# driver.net
KiCad netlist of a schematic drawn in EAGLE
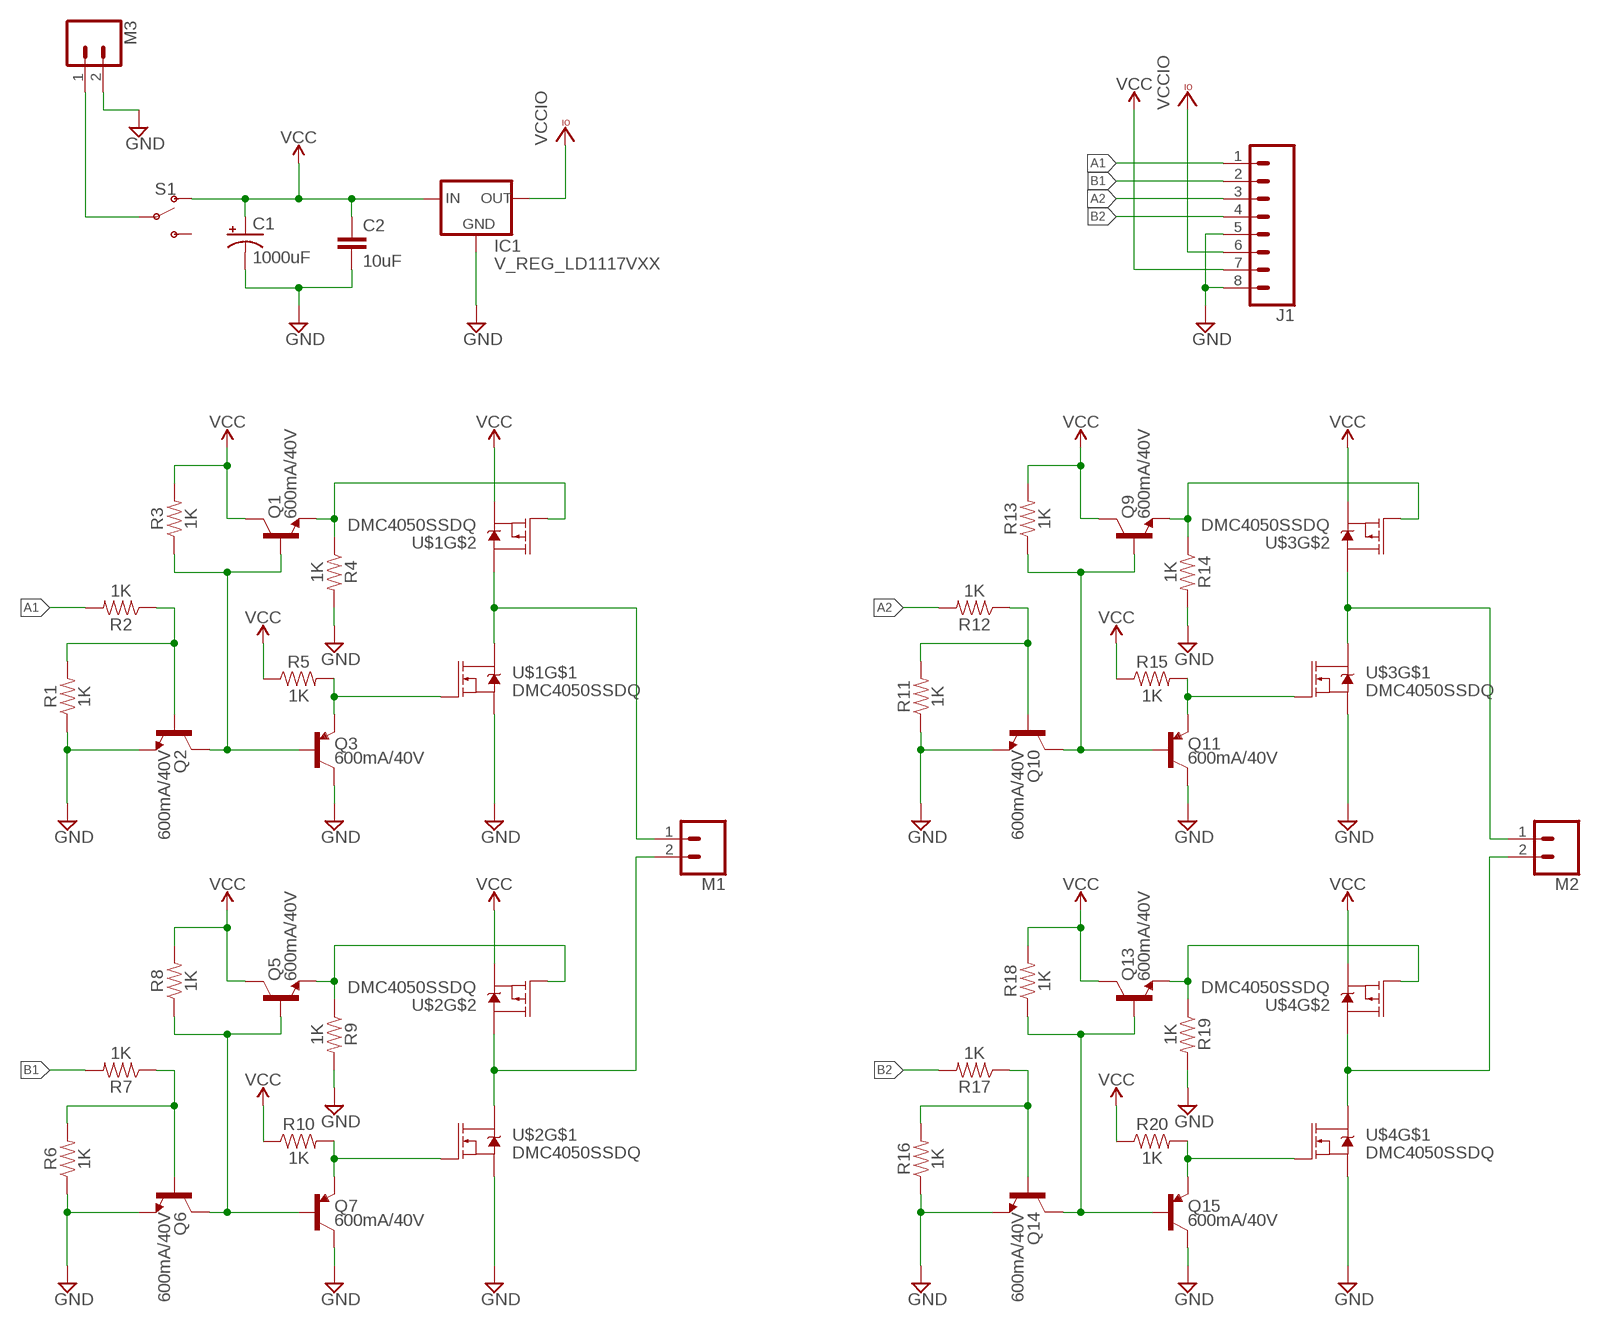
[diagram p0: schematic, sheet 1]

(export (version "E")
  (design (tool "Eeschema 10.0.6"))
  (components
    (comp (ref "C1")
      (value "1000uF")
      (footprint "eagle-import:CPOL-RADIAL-5MM-10MM")
      (libsource (lib "eagle-import") (part "1000UF-RADIAL-5MM-25V-20%"))
    )
    (comp (ref "C2")
      (value "10uF")
      (footprint "eagle-import:0805")
      (libsource (lib "eagle-import") (part "1.0UF-0805-25V-10%"))
    )
    (comp (ref "IC1")
      (value "V_REG_LD1117VXX")
      (footprint "eagle-import:78XXL")
      (libsource (lib "eagle-import") (part "V_REG_LD1117VXX"))
    )
    (comp (ref "J1")
      (value "CONN_08\"")
      (footprint "eagle-import:1X08")
      (libsource (lib "eagle-import") (part "CONN_08{dblquote}"))
    )
    (comp (ref "M1")
      (value "CONN_023.5MM")
      (footprint "eagle-import:SCREWTERMINAL-3.5MM-2")
      (libsource (lib "eagle-import") (part "CONN_023.5MM"))
    )
    (comp (ref "M2")
      (value "CONN_023.5MM")
      (footprint "eagle-import:SCREWTERMINAL-3.5MM-2")
      (libsource (lib "eagle-import") (part "CONN_023.5MM"))
    )
    (comp (ref "M3")
      (value "CONN_023.5MM")
      (footprint "eagle-import:SCREWTERMINAL-3.5MM-2")
      (libsource (lib "eagle-import") (part "CONN_023.5MM"))
    )
    (comp (ref "Q1")
      (value "600mA/40V")
      (footprint "eagle-import:SOT23-3")
      (libsource (lib "eagle-import") (part "TRANS_NPN-MMBT2222AL"))
    )
    (comp (ref "Q2")
      (value "600mA/40V")
      (footprint "eagle-import:SOT23-3")
      (libsource (lib "eagle-import") (part "TRANS_NPN-MMBT2222AL"))
    )
    (comp (ref "Q3")
      (value "600mA/40V")
      (footprint "eagle-import:SOT23-3")
      (libsource (lib "eagle-import") (part "TRANS_PNP-MMBT4403"))
    )
    (comp (ref "Q5")
      (value "600mA/40V")
      (footprint "eagle-import:SOT23-3")
      (libsource (lib "eagle-import") (part "TRANS_NPN-MMBT2222AL"))
    )
    (comp (ref "Q6")
      (value "600mA/40V")
      (footprint "eagle-import:SOT23-3")
      (libsource (lib "eagle-import") (part "TRANS_NPN-MMBT2222AL"))
    )
    (comp (ref "Q7")
      (value "600mA/40V")
      (footprint "eagle-import:SOT23-3")
      (libsource (lib "eagle-import") (part "TRANS_PNP-MMBT4403"))
    )
    (comp (ref "Q9")
      (value "600mA/40V")
      (footprint "eagle-import:SOT23-3")
      (libsource (lib "eagle-import") (part "TRANS_NPN-MMBT2222AL"))
    )
    (comp (ref "Q10")
      (value "600mA/40V")
      (footprint "eagle-import:SOT23-3")
      (libsource (lib "eagle-import") (part "TRANS_NPN-MMBT2222AL"))
    )
    (comp (ref "Q11")
      (value "600mA/40V")
      (footprint "eagle-import:SOT23-3")
      (libsource (lib "eagle-import") (part "TRANS_PNP-MMBT4403"))
    )
    (comp (ref "Q13")
      (value "600mA/40V")
      (footprint "eagle-import:SOT23-3")
      (libsource (lib "eagle-import") (part "TRANS_NPN-MMBT2222AL"))
    )
    (comp (ref "Q14")
      (value "600mA/40V")
      (footprint "eagle-import:SOT23-3")
      (libsource (lib "eagle-import") (part "TRANS_NPN-MMBT2222AL"))
    )
    (comp (ref "Q15")
      (value "600mA/40V")
      (footprint "eagle-import:SOT23-3")
      (libsource (lib "eagle-import") (part "TRANS_PNP-MMBT4403"))
    )
    (comp (ref "R1")
      (value "1K")
      (footprint "eagle-import:0805")
      (libsource (lib "eagle-import") (part "RESISTOR0805"))
    )
    (comp (ref "R2")
      (value "1K")
      (footprint "eagle-import:0805")
      (libsource (lib "eagle-import") (part "RESISTOR0805"))
    )
    (comp (ref "R3")
      (value "1K")
      (footprint "eagle-import:0805")
      (libsource (lib "eagle-import") (part "RESISTOR0805"))
    )
    (comp (ref "R4")
      (value "1K")
      (footprint "eagle-import:0805")
      (libsource (lib "eagle-import") (part "RESISTOR0805"))
    )
    (comp (ref "R5")
      (value "1K")
      (footprint "eagle-import:0805")
      (libsource (lib "eagle-import") (part "RESISTOR0805"))
    )
    (comp (ref "R6")
      (value "1K")
      (footprint "eagle-import:0805")
      (libsource (lib "eagle-import") (part "RESISTOR0805"))
    )
    (comp (ref "R7")
      (value "1K")
      (footprint "eagle-import:0805")
      (libsource (lib "eagle-import") (part "RESISTOR0805"))
    )
    (comp (ref "R8")
      (value "1K")
      (footprint "eagle-import:0805")
      (libsource (lib "eagle-import") (part "RESISTOR0805"))
    )
    (comp (ref "R9")
      (value "1K")
      (footprint "eagle-import:0805")
      (libsource (lib "eagle-import") (part "RESISTOR0805"))
    )
    (comp (ref "R10")
      (value "1K")
      (footprint "eagle-import:0805")
      (libsource (lib "eagle-import") (part "RESISTOR0805"))
    )
    (comp (ref "R11")
      (value "1K")
      (footprint "eagle-import:0805")
      (libsource (lib "eagle-import") (part "RESISTOR0805"))
    )
    (comp (ref "R12")
      (value "1K")
      (footprint "eagle-import:0805")
      (libsource (lib "eagle-import") (part "RESISTOR0805"))
    )
    (comp (ref "R13")
      (value "1K")
      (footprint "eagle-import:0805")
      (libsource (lib "eagle-import") (part "RESISTOR0805"))
    )
    (comp (ref "R14")
      (value "1K")
      (footprint "eagle-import:0805")
      (libsource (lib "eagle-import") (part "RESISTOR0805"))
    )
    (comp (ref "R15")
      (value "1K")
      (footprint "eagle-import:0805")
      (libsource (lib "eagle-import") (part "RESISTOR0805"))
    )
    (comp (ref "R16")
      (value "1K")
      (footprint "eagle-import:0805")
      (libsource (lib "eagle-import") (part "RESISTOR0805"))
    )
    (comp (ref "R17")
      (value "1K")
      (footprint "eagle-import:0805")
      (libsource (lib "eagle-import") (part "RESISTOR0805"))
    )
    (comp (ref "R18")
      (value "1K")
      (footprint "eagle-import:0805")
      (libsource (lib "eagle-import") (part "RESISTOR0805"))
    )
    (comp (ref "R19")
      (value "1K")
      (footprint "eagle-import:0805")
      (libsource (lib "eagle-import") (part "RESISTOR0805"))
    )
    (comp (ref "R20")
      (value "1K")
      (footprint "eagle-import:0805")
      (libsource (lib "eagle-import") (part "RESISTOR0805"))
    )
    (comp (ref "S1")
      (value "SWITCH-SPDT-PTH-11.6X4.0MM")
      (footprint "eagle-import:SWITCH_SPDT_PTH_11.6X4.0MM")
      (libsource (lib "eagle-import") (part "SWITCH-SPDT-PTH-11.6X4.0MM"))
    )
    (comp (ref "U$1")
      (value "DMC4050SSDQ")
      (footprint "eagle-import:SO08")
      (libsource (lib "eagle-import") (part "DMC4050SSDQ"))
    )
    (comp (ref "U$2")
      (value "DMC4050SSDQ")
      (footprint "eagle-import:SO08")
      (libsource (lib "eagle-import") (part "DMC4050SSDQ"))
    )
    (comp (ref "U$3")
      (value "DMC4050SSDQ")
      (footprint "eagle-import:SO08")
      (libsource (lib "eagle-import") (part "DMC4050SSDQ"))
    )
    (comp (ref "U$4")
      (value "DMC4050SSDQ")
      (footprint "eagle-import:SO08")
      (libsource (lib "eagle-import") (part "DMC4050SSDQ"))
    )
  )
  (nets
    (net (code "1") (name "A1") (class "Default")
      (node (ref "J1") (pin "1") (pinfunction "1_1") (pintype "passive"))
      (node (ref "R2") (pin "2") (pinfunction "2_2") (pintype "passive"))
    )
    (net (code "2") (name "A2") (class "Default")
      (node (ref "J1") (pin "3") (pinfunction "3_3") (pintype "passive"))
      (node (ref "R12") (pin "2") (pinfunction "2_2") (pintype "passive"))
    )
    (net (code "3") (name "B1") (class "Default")
      (node (ref "J1") (pin "2") (pinfunction "2_2") (pintype "passive"))
      (node (ref "R7") (pin "2") (pinfunction "2_2") (pintype "passive"))
    )
    (net (code "4") (name "B2") (class "Default")
      (node (ref "J1") (pin "4") (pinfunction "4_4") (pintype "passive"))
      (node (ref "R17") (pin "2") (pinfunction "2_2") (pintype "passive"))
    )
    (net (code "5") (name "GND") (class "Default")
      (node (ref "C1") (pin "-") (pinfunction "-_-") (pintype "passive"))
      (node (ref "C2") (pin "2") (pinfunction "2_2") (pintype "passive"))
      (node (ref "IC1") (pin "IN") (pinfunction "GND_IN") (pintype "input"))
      (node (ref "J1") (pin "5") (pinfunction "5_5") (pintype "passive"))
      (node (ref "J1") (pin "8") (pinfunction "8_8") (pintype "passive"))
      (node (ref "M3") (pin "2") (pinfunction "2_2") (pintype "passive"))
      (node (ref "Q10") (pin "2") (pinfunction "E_2") (pintype "passive"))
      (node (ref "Q11") (pin "3") (pinfunction "C_3") (pintype "passive"))
      (node (ref "Q14") (pin "2") (pinfunction "E_2") (pintype "passive"))
      (node (ref "Q15") (pin "3") (pinfunction "C_3") (pintype "passive"))
      (node (ref "Q2") (pin "2") (pinfunction "E_2") (pintype "passive"))
      (node (ref "Q3") (pin "3") (pinfunction "C_3") (pintype "passive"))
      (node (ref "Q6") (pin "2") (pinfunction "E_2") (pintype "passive"))
      (node (ref "Q7") (pin "3") (pinfunction "C_3") (pintype "passive"))
      (node (ref "R1") (pin "1") (pinfunction "1_1") (pintype "passive"))
      (node (ref "R11") (pin "1") (pinfunction "1_1") (pintype "passive"))
      (node (ref "R14") (pin "2") (pinfunction "2_2") (pintype "passive"))
      (node (ref "R16") (pin "1") (pinfunction "1_1") (pintype "passive"))
      (node (ref "R19") (pin "2") (pinfunction "2_2") (pintype "passive"))
      (node (ref "R4") (pin "2") (pinfunction "2_2") (pintype "passive"))
      (node (ref "R6") (pin "1") (pinfunction "1_1") (pintype "passive"))
      (node (ref "R9") (pin "2") (pinfunction "2_2") (pintype "passive"))
      (node (ref "U$1") (pin "1") (pinfunction "S_1") (pintype "bidirectional"))
      (node (ref "U$2") (pin "1") (pinfunction "S_1") (pintype "bidirectional"))
      (node (ref "U$3") (pin "1") (pinfunction "S_1") (pintype "bidirectional"))
      (node (ref "U$4") (pin "1") (pinfunction "S_1") (pintype "bidirectional"))
    )
    (net (code "6") (name "Net-(M1-Pad1)") (class "Default")
      (node (ref "M1") (pin "1") (pinfunction "1_1") (pintype "passive"))
      (node (ref "U$1") (pin "5") (pinfunction "D_5") (pintype "bidirectional"))
      (node (ref "U$1") (pin "6") (pinfunction "D_6") (pintype "bidirectional"))
      (node (ref "U$1") (pin "7") (pinfunction "D_7") (pintype "bidirectional"))
      (node (ref "U$1") (pin "8") (pinfunction "D_8") (pintype "bidirectional"))
    )
    (net (code "7") (name "Net-(M1-Pad2)") (class "Default")
      (node (ref "M1") (pin "2") (pinfunction "2_2") (pintype "passive"))
      (node (ref "U$2") (pin "5") (pinfunction "D_5") (pintype "bidirectional"))
      (node (ref "U$2") (pin "6") (pinfunction "D_6") (pintype "bidirectional"))
      (node (ref "U$2") (pin "7") (pinfunction "D_7") (pintype "bidirectional"))
      (node (ref "U$2") (pin "8") (pinfunction "D_8") (pintype "bidirectional"))
    )
    (net (code "8") (name "Net-(M2-Pad1)") (class "Default")
      (node (ref "M2") (pin "1") (pinfunction "1_1") (pintype "passive"))
      (node (ref "U$3") (pin "5") (pinfunction "D_5") (pintype "bidirectional"))
      (node (ref "U$3") (pin "6") (pinfunction "D_6") (pintype "bidirectional"))
      (node (ref "U$3") (pin "7") (pinfunction "D_7") (pintype "bidirectional"))
      (node (ref "U$3") (pin "8") (pinfunction "D_8") (pintype "bidirectional"))
    )
    (net (code "9") (name "Net-(M2-Pad2)") (class "Default")
      (node (ref "M2") (pin "2") (pinfunction "2_2") (pintype "passive"))
      (node (ref "U$4") (pin "5") (pinfunction "D_5") (pintype "bidirectional"))
      (node (ref "U$4") (pin "6") (pinfunction "D_6") (pintype "bidirectional"))
      (node (ref "U$4") (pin "7") (pinfunction "D_7") (pintype "bidirectional"))
      (node (ref "U$4") (pin "8") (pinfunction "D_8") (pintype "bidirectional"))
    )
    (net (code "10") (name "Net-(Q1-B)") (class "Default")
      (node (ref "Q1") (pin "1") (pinfunction "B_1") (pintype "passive"))
      (node (ref "Q2") (pin "3") (pinfunction "C_3") (pintype "passive"))
      (node (ref "Q3") (pin "1") (pinfunction "B_1") (pintype "passive"))
      (node (ref "R3") (pin "1") (pinfunction "1_1") (pintype "passive"))
    )
    (net (code "11") (name "Net-(Q1-E)") (class "Default")
      (node (ref "Q1") (pin "2") (pinfunction "E_2") (pintype "passive"))
      (node (ref "R4") (pin "1") (pinfunction "1_1") (pintype "passive"))
      (node (ref "U$1") (pin "4") (pinfunction "G_4") (pintype "bidirectional"))
    )
    (net (code "12") (name "Net-(Q2-B)") (class "Default")
      (node (ref "Q2") (pin "1") (pinfunction "B_1") (pintype "passive"))
      (node (ref "R1") (pin "2") (pinfunction "2_2") (pintype "passive"))
      (node (ref "R2") (pin "1") (pinfunction "1_1") (pintype "passive"))
    )
    (net (code "13") (name "Net-(Q3-E)") (class "Default")
      (node (ref "Q3") (pin "2") (pinfunction "E_2") (pintype "passive"))
      (node (ref "R5") (pin "2") (pinfunction "2_2") (pintype "passive"))
      (node (ref "U$1") (pin "2") (pinfunction "G_2") (pintype "bidirectional"))
    )
    (net (code "14") (name "Net-(Q5-B)") (class "Default")
      (node (ref "Q5") (pin "1") (pinfunction "B_1") (pintype "passive"))
      (node (ref "Q6") (pin "3") (pinfunction "C_3") (pintype "passive"))
      (node (ref "Q7") (pin "1") (pinfunction "B_1") (pintype "passive"))
      (node (ref "R8") (pin "1") (pinfunction "1_1") (pintype "passive"))
    )
    (net (code "15") (name "Net-(Q5-E)") (class "Default")
      (node (ref "Q5") (pin "2") (pinfunction "E_2") (pintype "passive"))
      (node (ref "R9") (pin "1") (pinfunction "1_1") (pintype "passive"))
      (node (ref "U$2") (pin "4") (pinfunction "G_4") (pintype "bidirectional"))
    )
    (net (code "16") (name "Net-(Q6-B)") (class "Default")
      (node (ref "Q6") (pin "1") (pinfunction "B_1") (pintype "passive"))
      (node (ref "R6") (pin "2") (pinfunction "2_2") (pintype "passive"))
      (node (ref "R7") (pin "1") (pinfunction "1_1") (pintype "passive"))
    )
    (net (code "17") (name "Net-(Q7-E)") (class "Default")
      (node (ref "Q7") (pin "2") (pinfunction "E_2") (pintype "passive"))
      (node (ref "R10") (pin "2") (pinfunction "2_2") (pintype "passive"))
      (node (ref "U$2") (pin "2") (pinfunction "G_2") (pintype "bidirectional"))
    )
    (net (code "18") (name "Net-(Q9-E)") (class "Default")
      (node (ref "Q9") (pin "2") (pinfunction "E_2") (pintype "passive"))
      (node (ref "R14") (pin "1") (pinfunction "1_1") (pintype "passive"))
      (node (ref "U$3") (pin "4") (pinfunction "G_4") (pintype "bidirectional"))
    )
    (net (code "19") (name "Net-(Q10-B)") (class "Default")
      (node (ref "Q10") (pin "1") (pinfunction "B_1") (pintype "passive"))
      (node (ref "R11") (pin "2") (pinfunction "2_2") (pintype "passive"))
      (node (ref "R12") (pin "1") (pinfunction "1_1") (pintype "passive"))
    )
    (net (code "20") (name "Net-(Q10-C)") (class "Default")
      (node (ref "Q10") (pin "3") (pinfunction "C_3") (pintype "passive"))
      (node (ref "Q11") (pin "1") (pinfunction "B_1") (pintype "passive"))
      (node (ref "Q9") (pin "1") (pinfunction "B_1") (pintype "passive"))
      (node (ref "R13") (pin "1") (pinfunction "1_1") (pintype "passive"))
    )
    (net (code "21") (name "Net-(Q11-E)") (class "Default")
      (node (ref "Q11") (pin "2") (pinfunction "E_2") (pintype "passive"))
      (node (ref "R15") (pin "2") (pinfunction "2_2") (pintype "passive"))
      (node (ref "U$3") (pin "2") (pinfunction "G_2") (pintype "bidirectional"))
    )
    (net (code "22") (name "Net-(Q13-B)") (class "Default")
      (node (ref "Q13") (pin "1") (pinfunction "B_1") (pintype "passive"))
      (node (ref "Q14") (pin "3") (pinfunction "C_3") (pintype "passive"))
      (node (ref "Q15") (pin "1") (pinfunction "B_1") (pintype "passive"))
      (node (ref "R18") (pin "1") (pinfunction "1_1") (pintype "passive"))
    )
    (net (code "23") (name "Net-(Q13-E)") (class "Default")
      (node (ref "Q13") (pin "2") (pinfunction "E_2") (pintype "passive"))
      (node (ref "R19") (pin "1") (pinfunction "1_1") (pintype "passive"))
      (node (ref "U$4") (pin "4") (pinfunction "G_4") (pintype "bidirectional"))
    )
    (net (code "24") (name "Net-(Q14-B)") (class "Default")
      (node (ref "Q14") (pin "1") (pinfunction "B_1") (pintype "passive"))
      (node (ref "R16") (pin "2") (pinfunction "2_2") (pintype "passive"))
      (node (ref "R17") (pin "1") (pinfunction "1_1") (pintype "passive"))
    )
    (net (code "25") (name "Net-(Q15-E)") (class "Default")
      (node (ref "Q15") (pin "2") (pinfunction "E_2") (pintype "passive"))
      (node (ref "R20") (pin "2") (pinfunction "2_2") (pintype "passive"))
      (node (ref "U$4") (pin "2") (pinfunction "G_2") (pintype "bidirectional"))
    )
    (net (code "26") (name "Net-(S1-P)") (class "Default")
      (node (ref "M3") (pin "1") (pinfunction "1_1") (pintype "passive"))
      (node (ref "S1") (pin "2") (pinfunction "P_2") (pintype "passive"))
    )
    (net (code "27") (name "VCC") (class "Default")
      (node (ref "C1") (pin "+") (pinfunction "+_+") (pintype "passive"))
      (node (ref "C2") (pin "1") (pinfunction "1_1") (pintype "passive"))
      (node (ref "IC1") (pin "OUT") (pinfunction "IN_OUT") (pintype "input"))
      (node (ref "J1") (pin "7") (pinfunction "7_7") (pintype "passive"))
      (node (ref "Q1") (pin "3") (pinfunction "C_3") (pintype "passive"))
      (node (ref "Q13") (pin "3") (pinfunction "C_3") (pintype "passive"))
      (node (ref "Q5") (pin "3") (pinfunction "C_3") (pintype "passive"))
      (node (ref "Q9") (pin "3") (pinfunction "C_3") (pintype "passive"))
      (node (ref "R10") (pin "1") (pinfunction "1_1") (pintype "passive"))
      (node (ref "R13") (pin "2") (pinfunction "2_2") (pintype "passive"))
      (node (ref "R15") (pin "1") (pinfunction "1_1") (pintype "passive"))
      (node (ref "R18") (pin "2") (pinfunction "2_2") (pintype "passive"))
      (node (ref "R20") (pin "1") (pinfunction "1_1") (pintype "passive"))
      (node (ref "R3") (pin "2") (pinfunction "2_2") (pintype "passive"))
      (node (ref "R5") (pin "1") (pinfunction "1_1") (pintype "passive"))
      (node (ref "R8") (pin "2") (pinfunction "2_2") (pintype "passive"))
      (node (ref "S1") (pin "1") (pinfunction "O_1") (pintype "passive"))
      (node (ref "U$1") (pin "3") (pinfunction "S_3") (pintype "bidirectional"))
      (node (ref "U$2") (pin "3") (pinfunction "S_3") (pintype "bidirectional"))
      (node (ref "U$3") (pin "3") (pinfunction "S_3") (pintype "bidirectional"))
      (node (ref "U$4") (pin "3") (pinfunction "S_3") (pintype "bidirectional"))
    )
    (net (code "28") (name "VCCIO") (class "Default")
      (node (ref "IC1") (pin "GND") (pinfunction "OUT_GND") (pintype "passive"))
      (node (ref "J1") (pin "6") (pinfunction "6_6") (pintype "passive"))
    )
    (net (code "29") (name "unconnected-(S1-S-Pad3)") (class "Default")
      (node (ref "S1") (pin "3") (pinfunction "S_3") (pintype "passive"))
    )
  )
)
